# main_master.net
KiCad netlist of a schematic drawn in Altium Designer
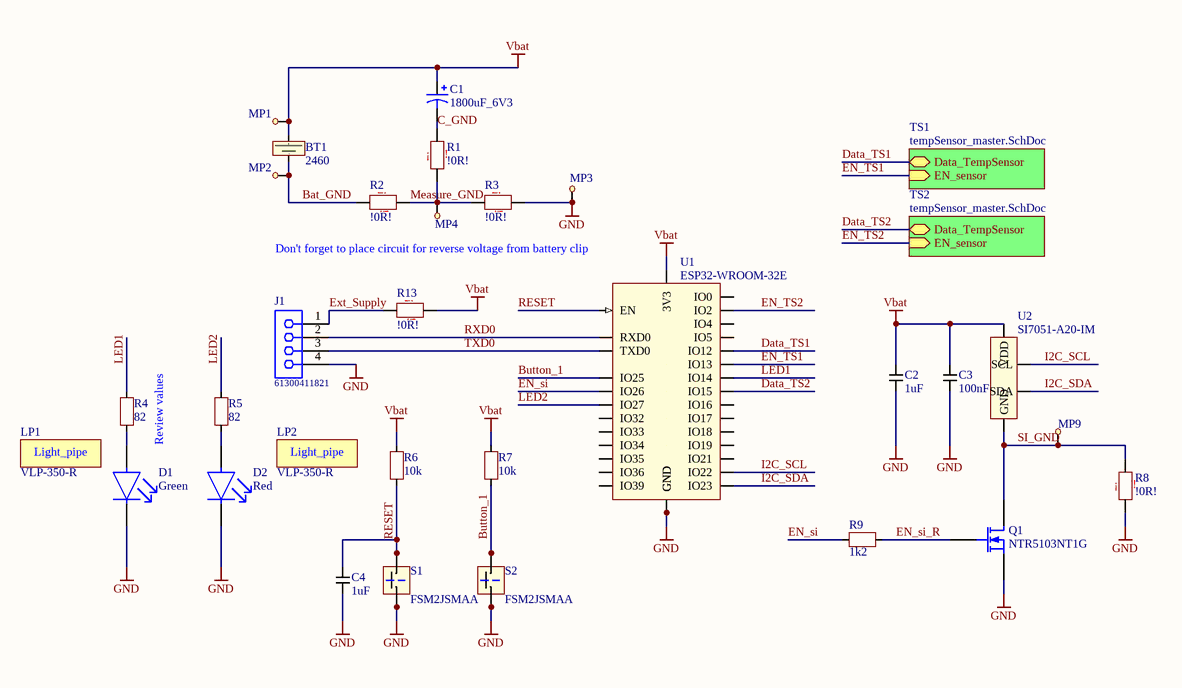
[diagram p0: main_master.SchDoc]

(export (version "E")
  (design (tool "Eeschema 10.0.6"))
  (components
    (comp (ref "BT1")
      (value "2460")
      (footprint "KEYSTONE_2410")
      (description "Battery Holder, AA x 1, Through Hole")
      (libsource (lib "Misc") (part "2460"))
    )
    (comp (ref "C1")
      (value "1800uF_6V3")
      (footprint "CAPAE109103X105M")
      (description "SMD Aluminium Electrolytic Capacitor, Radial Can, 1800 µF, 10 V, 0.092 ohm, TRV Series")
      (fields
        (field (name "MANUFACTURER PART NUMBER") "EEE-FN0J182UV")
        (field (name "MANUFACTURER") "Panasonic")
      )
      (libsource (lib "Capacitors_electrolytic") (part "1800uF_6V3"))
    )
    (comp (ref "C2")
      (value "1uF")
      (footprint "C1206")
      (description "1uF, 1206")
      (libsource (lib "Capacitors") (part "1uF,1206"))
    )
    (comp (ref "C3")
      (value "100nF")
      (footprint "C1206")
      (description "100nF, 1206")
      (libsource (lib "Capacitors") (part "100nF,1206"))
    )
    (comp (ref "C4")
      (value "1uF")
      (footprint "C1206")
      (description "1uF, 1206")
      (libsource (lib "Capacitors") (part "1uF,1206"))
    )
    (comp (ref "D1")
      (value "Green")
      (footprint "Kingbright_KPT-2012EC_0")
      (description "Standard LEDs - SMD GRN WATER CLEAR 0805")
      (fields
        (field (name "MANUFACTURER") "Kingbright")
        (field (name "MANUFACTURER PART NUMBER") "AP2012MGC")
      )
      (libsource (lib "LED_AND_DISPLAYS") (part "AP2012MGC"))
    )
    (comp (ref "D2")
      (value "Red")
      (footprint "Kingbright_KPT-2012EC_0")
      (description "KPT-2012EC -  LED, Low Power, Red, SMD, 0805 [2012 Metric], 30 mA, 2 V, 617 nm")
      (libsource (lib "LED_AND_DISPLAYS") (part "KPT-2012EC"))
    )
    (comp (ref "J1")
      (value "61300411821")
      (footprint "61300411821")
      (description "THT Vertical Socket Header WR-PHD, Pitch 2.54 mm, Single Row, 4 pins")
      (fields (field (name "PUBLISHER") "Wurth Elektronik"))
      (libsource (lib "Connectoren") (part "61300411821"))
    )
    (comp (ref "LP1")
      (value "VLP-350-R")
      (footprint "VLP-350-R")
      (description "LIGHT PIPE, SINGLE, ROUND, PCB")
      (fields (field (name "MANUFACTURER") "BIVAR"))
      (libsource (lib "Light_Pipes") (part "VLP-350-R"))
    )
    (comp (ref "LP2")
      (value "VLP-350-R")
      (footprint "VLP-350-R")
      (description "LIGHT PIPE, SINGLE, ROUND, PCB")
      (fields (field (name "MANUFACTURER") "BIVAR"))
      (libsource (lib "Light_Pipes") (part "VLP-350-R"))
    )
    (comp (ref "MP1")
      (value "Measure_point")
      (footprint "MeasurePoint_1.5mm")
      (description "Measurepoint")
      (libsource (lib "Misc") (part "Measure_point"))
    )
    (comp (ref "MP2")
      (value "Measure_point")
      (footprint "MeasurePoint_1.5mm")
      (description "Measurepoint")
      (libsource (lib "Misc") (part "Measure_point"))
    )
    (comp (ref "MP3")
      (value "Measure_point")
      (footprint "MeasurePoint_1.5mm")
      (description "Measurepoint")
      (libsource (lib "Misc") (part "Measure_point"))
    )
    (comp (ref "MP4")
      (value "Measure_point")
      (footprint "MeasurePoint_1.5mm")
      (description "Measurepoint")
      (libsource (lib "Misc") (part "Measure_point"))
    )
    (comp (ref "MP9")
      (value "Measure_point")
      (footprint "MeasurePoint_1.5mm")
      (description "Measurepoint")
      (libsource (lib "Misc") (part "Measure_point"))
    )
    (comp (ref "Q1")
      (value "NTR5103NT1G")
      (footprint "SOT23")
      (description "Power MOSFET, N Channel, 60 V, 260 mA, 1 ohm, SOT-23, Surface Mount")
      (fields (field (name "MANUFACTURER") "ON Semiconductor"))
      (libsource (lib "MOSFETS") (part "NTR5103NT1G"))
    )
    (comp (ref "R1")
      (value "!0R!")
      (footprint "R1206_Simple-Assemble")
      (description "normally shorted, but easy to change to an resistor footprint")
      (libsource (lib "") (part "0R, optional resistor_1"))
    )
    (comp (ref "R2")
      (value "!0R!")
      (footprint "R1206_Simple-Assemble")
      (description "normally shorted, but easy to change to an resistor footprint")
      (libsource (lib "Resistors") (part "0R, optional resistor"))
    )
    (comp (ref "R3")
      (value "!0R!")
      (footprint "R1206_Simple-Assemble")
      (description "normally shorted, but easy to change to an resistor footprint")
      (libsource (lib "Resistors") (part "0R, optional resistor"))
    )
    (comp (ref "R4")
      (value "82")
      (footprint "R1206_Simple-Assemble")
      (libsource (lib "Resistors") (part "82, 1206"))
    )
    (comp (ref "R5")
      (value "82")
      (footprint "R1206_Simple-Assemble")
      (libsource (lib "Resistors") (part "82, 1206"))
    )
    (comp (ref "R6")
      (value "10k")
      (footprint "R1206_Simple-Assemble")
      (description "10k, 1206, 250mW, 200V")
      (fields (field (name "POWER") "250mW"))
      (libsource (lib "Resistors") (part "10k, 1206"))
    )
    (comp (ref "R7")
      (value "10k")
      (footprint "R1206_Simple-Assemble")
      (description "10k, 1206, 250mW, 200V")
      (fields (field (name "POWER") "250mW"))
      (libsource (lib "Resistors") (part "10k, 1206"))
    )
    (comp (ref "R8")
      (value "!0R!")
      (footprint "R1206_Simple-Assemble")
      (description "normally shorted, but easy to change to an resistor footprint")
      (libsource (lib "") (part "0R, optional resistor_1"))
    )
    (comp (ref "R9")
      (value "1k2")
      (footprint "R1206_Simple-Assemble")
      (description "SMD Chip Resistor, 1206 [3216 Metric], 1 kohm, MCSR 12 Series, 200 V, Ceramic, 250 mW")
      (fields (field (name "POWER") "250mW"))
      (libsource (lib "Resistors") (part "1k2, 1206"))
    )
    (comp (ref "R13")
      (value "!0R!")
      (footprint "R1206_Simple-Assemble")
      (description "normally shorted, but easy to change to an resistor footprint")
      (libsource (lib "Resistors") (part "0R, optional resistor"))
    )
    (comp (ref "S1")
      (value "FSM2JSMAA")
      (footprint "FP-FSM2JSMAA-MFG")
      (description "Tactile Switch, FSMJSM Series, Top Actuated, Surface Mount, Round Button, 260 gf, 50mA at 24VDC")
      (fields (field (name "MANUFACTURER") "TE Connectivity"))
      (libsource (lib "Misc") (part "FSM2JSMAA"))
    )
    (comp (ref "S2")
      (value "FSM2JSMAA")
      (footprint "FP-FSM2JSMAA-MFG")
      (description "Tactile Switch, FSMJSM Series, Top Actuated, Surface Mount, Round Button, 260 gf, 50mA at 24VDC")
      (fields (field (name "MANUFACTURER") "TE Connectivity"))
      (libsource (lib "Misc") (part "FSM2JSMAA"))
    )
    (comp (ref "U1")
      (value "ESP32-WROOM-32E")
      (footprint "ESP32­WROOM­32E")
      (description "USB-modules (802.11) SMD Module ESP32-WROOM-32E, ESP32-D0WD-V3, 16 MB SPI flash, PCB antenna")
      (libsource (lib "Misc") (part "ESP32-WROOM-32E(M113EH2800PH3Q0)"))
    )
    (comp (ref "U2")
      (value "SI7051-A20-IM")
      (footprint "3x3 6-pin DFN")
      (description "Temperature Sensor IC, Digital, ± 0.1°C, -40 °C, 125 °C, DFN, 6 Pins")
      (libsource (lib "IC's") (part "SI7051-A20-IM"))
    )
  )
  (nets
    (net (code "1") (name "/Bat_GND") (class "Default")
      (node (ref "BT1") (pin "2") (pinfunction "-_2") (pintype "passive"))
      (node (ref "MP2") (pin "1") (pinfunction "1_1") (pintype "passive"))
      (node (ref "R2") (pin "1") (pinfunction "1_1") (pintype "passive"))
    )
    (net (code "2") (name "/Button_1") (class "Default")
      (node (ref "R7") (pin "1") (pinfunction "1_1") (pintype "passive"))
      (node (ref "S2") (pin "2") (pinfunction "b_2") (pintype "passive"))
      (node (ref "S2") (pin "4") (pinfunction "d_4") (pintype "passive"))
      (node (ref "U1") (pin "10") (pinfunction "IO25_10") (pintype "bidirectional"))
    )
    (net (code "3") (name "/C_GND") (class "Default")
      (node (ref "C1") (pin "2") (pinfunction "2_2") (pintype "passive"))
      (node (ref "R1") (pin "2") (pinfunction "2_2") (pintype "passive"))
    )
    (net (code "4") (name "/Data_TS1") (class "Default")
      (node (ref "U1") (pin "14") (pinfunction "IO12_14") (pintype "bidirectional"))
    )
    (net (code "5") (name "/Data_TS2") (class "Default")
      (node (ref "U1") (pin "23") (pinfunction "IO15_23") (pintype "bidirectional"))
    )
    (net (code "6") (name "/EN_TS1") (class "Default")
      (node (ref "U1") (pin "16") (pinfunction "IO13_16") (pintype "bidirectional"))
    )
    (net (code "7") (name "/EN_TS2") (class "Default")
      (node (ref "U1") (pin "24") (pinfunction "IO2_24") (pintype "bidirectional"))
    )
    (net (code "8") (name "/EN_si") (class "Default")
      (node (ref "R9") (pin "1") (pinfunction "1_1") (pintype "passive"))
      (node (ref "U1") (pin "11") (pinfunction "IO26_11") (pintype "bidirectional"))
    )
    (net (code "9") (name "/EN_si_R") (class "Default")
      (node (ref "Q1") (pin "1") (pinfunction "G_1") (pintype "passive"))
      (node (ref "R9") (pin "2") (pinfunction "2_2") (pintype "passive"))
    )
    (net (code "10") (name "/Ext_Supply") (class "Default")
      (node (ref "J1") (pin "1") (pinfunction "1_1") (pintype "passive"))
      (node (ref "R13") (pin "1") (pinfunction "1_1") (pintype "passive"))
    )
    (net (code "11") (name "/I2C_SCL") (class "Default")
      (node (ref "U1") (pin "36") (pinfunction "IO22_36") (pintype "bidirectional"))
      (node (ref "U2") (pin "6") (pinfunction "SCL_6") (pintype "bidirectional"))
    )
    (net (code "12") (name "/I2C_SDA") (class "Default")
      (node (ref "U1") (pin "37") (pinfunction "IO23_37") (pintype "bidirectional"))
      (node (ref "U2") (pin "1") (pinfunction "SDA_1") (pintype "bidirectional"))
    )
    (net (code "13") (name "/LED1") (class "Default")
      (node (ref "R4") (pin "2") (pinfunction "2_2") (pintype "passive"))
      (node (ref "U1") (pin "13") (pinfunction "IO14_13") (pintype "bidirectional"))
    )
    (net (code "14") (name "/LED2") (class "Default")
      (node (ref "R5") (pin "2") (pinfunction "2_2") (pintype "passive"))
      (node (ref "U1") (pin "12") (pinfunction "IO27_12") (pintype "bidirectional"))
    )
    (net (code "15") (name "/Measure_GND") (class "Default")
      (node (ref "MP4") (pin "1") (pinfunction "1_1") (pintype "passive"))
      (node (ref "R1") (pin "1") (pinfunction "1_1") (pintype "passive"))
      (node (ref "R2") (pin "2") (pinfunction "2_2") (pintype "passive"))
      (node (ref "R3") (pin "1") (pinfunction "1_1") (pintype "passive"))
    )
    (net (code "16") (name "/RESET") (class "Default")
      (node (ref "C4") (pin "2") (pinfunction "2_2") (pintype "passive"))
      (node (ref "R6") (pin "1") (pinfunction "1_1") (pintype "passive"))
      (node (ref "S1") (pin "2") (pinfunction "b_2") (pintype "passive"))
      (node (ref "S1") (pin "4") (pinfunction "d_4") (pintype "passive"))
      (node (ref "U1") (pin "3") (pinfunction "EN_3") (pintype "input"))
    )
    (net (code "17") (name "/RXD0") (class "Default")
      (node (ref "J1") (pin "2") (pinfunction "2_2") (pintype "passive"))
      (node (ref "U1") (pin "34") (pinfunction "RXD0_34") (pintype "bidirectional"))
    )
    (net (code "18") (name "/SI_GND") (class "Default")
      (node (ref "MP9") (pin "1") (pinfunction "1_1") (pintype "passive"))
      (node (ref "Q1") (pin "3") (pinfunction "D_3") (pintype "passive"))
      (node (ref "R8") (pin "2") (pinfunction "2_2") (pintype "passive"))
      (node (ref "U2") (pin "2") (pinfunction "GND_2") (pintype "power_in"))
    )
    (net (code "19") (name "/TXD0") (class "Default")
      (node (ref "J1") (pin "3") (pinfunction "3_3") (pintype "passive"))
      (node (ref "U1") (pin "35") (pinfunction "TXD0_35") (pintype "bidirectional"))
    )
    (net (code "20") (name "GND") (class "Default")
      (node (ref "C2") (pin "1") (pinfunction "1_1") (pintype "passive"))
      (node (ref "C3") (pin "1") (pinfunction "1_1") (pintype "passive"))
      (node (ref "C4") (pin "1") (pinfunction "1_1") (pintype "passive"))
      (node (ref "D1") (pin "1") (pinfunction "C_1") (pintype "passive"))
      (node (ref "D2") (pin "1") (pinfunction "C_1") (pintype "passive"))
      (node (ref "J1") (pin "4") (pinfunction "4_4") (pintype "passive"))
      (node (ref "MP3") (pin "1") (pinfunction "1_1") (pintype "passive"))
      (node (ref "Q1") (pin "2") (pinfunction "S_2") (pintype "passive"))
      (node (ref "R3") (pin "2") (pinfunction "2_2") (pintype "passive"))
      (node (ref "R8") (pin "1") (pinfunction "1_1") (pintype "passive"))
      (node (ref "S1") (pin "1") (pinfunction "a_1") (pintype "passive"))
      (node (ref "S1") (pin "3") (pinfunction "c_3") (pintype "passive"))
      (node (ref "S2") (pin "1") (pinfunction "a_1") (pintype "passive"))
      (node (ref "S2") (pin "3") (pinfunction "c_3") (pintype "passive"))
      (node (ref "U1") (pin "1") (pinfunction "GND_1") (pintype "power_in"))
      (node (ref "U1") (pin "15") (pinfunction "GND_15") (pintype "power_in"))
      (node (ref "U1") (pin "38") (pinfunction "GND_38") (pintype "power_in"))
    )
    (net (code "21") (name "Net-(D1-A)") (class "Default")
      (node (ref "D1") (pin "2") (pinfunction "A_2") (pintype "passive"))
      (node (ref "R4") (pin "1") (pinfunction "1_1") (pintype "passive"))
    )
    (net (code "22") (name "Net-(D2-A)") (class "Default")
      (node (ref "D2") (pin "2") (pinfunction "A_2") (pintype "passive"))
      (node (ref "R5") (pin "1") (pinfunction "1_1") (pintype "passive"))
    )
    (net (code "23") (name "Vbat") (class "Default")
      (node (ref "BT1") (pin "1") (pinfunction "+_1") (pintype "passive"))
      (node (ref "C1") (pin "1") (pinfunction "1_1") (pintype "passive"))
      (node (ref "C2") (pin "2") (pinfunction "2_2") (pintype "passive"))
      (node (ref "C3") (pin "2") (pinfunction "2_2") (pintype "passive"))
      (node (ref "MP1") (pin "1") (pinfunction "1_1") (pintype "passive"))
      (node (ref "R13") (pin "2") (pinfunction "2_2") (pintype "passive"))
      (node (ref "R6") (pin "2") (pinfunction "2_2") (pintype "passive"))
      (node (ref "R7") (pin "2") (pinfunction "2_2") (pintype "passive"))
      (node (ref "U1") (pin "2") (pinfunction "3V3_2") (pintype "power_in"))
      (node (ref "U2") (pin "5") (pinfunction "VDD_5") (pintype "power_in"))
    )
    (net (code "24") (name "unconnected-(U1-IO0-Pad25)") (class "Default")
      (node (ref "U1") (pin "25") (pinfunction "IO0_25") (pintype "bidirectional"))
    )
    (net (code "25") (name "unconnected-(U1-IO4-Pad26)") (class "Default")
      (node (ref "U1") (pin "26") (pinfunction "IO4_26") (pintype "bidirectional"))
    )
    (net (code "26") (name "unconnected-(U1-IO5-Pad29)") (class "Default")
      (node (ref "U1") (pin "29") (pinfunction "IO5_29") (pintype "bidirectional"))
    )
    (net (code "27") (name "unconnected-(U1-IO16-Pad27)") (class "Default")
      (node (ref "U1") (pin "27") (pinfunction "IO16_27") (pintype "bidirectional"))
    )
    (net (code "28") (name "unconnected-(U1-IO17-Pad28)") (class "Default")
      (node (ref "U1") (pin "28") (pinfunction "IO17_28") (pintype "bidirectional"))
    )
    (net (code "29") (name "unconnected-(U1-IO18-Pad30)") (class "Default")
      (node (ref "U1") (pin "30") (pinfunction "IO18_30") (pintype "bidirectional"))
    )
    (net (code "30") (name "unconnected-(U1-IO19-Pad31)") (class "Default")
      (node (ref "U1") (pin "31") (pinfunction "IO19_31") (pintype "bidirectional"))
    )
    (net (code "31") (name "unconnected-(U1-IO21-Pad33)") (class "Default")
      (node (ref "U1") (pin "33") (pinfunction "IO21_33") (pintype "bidirectional"))
    )
    (net (code "32") (name "unconnected-(U1-IO32-Pad8)") (class "Default")
      (node (ref "U1") (pin "8") (pinfunction "IO32_8") (pintype "bidirectional"))
    )
    (net (code "33") (name "unconnected-(U1-IO33-Pad9)") (class "Default")
      (node (ref "U1") (pin "9") (pinfunction "IO33_9") (pintype "bidirectional"))
    )
    (net (code "34") (name "unconnected-(U1-IO34-Pad6)") (class "Default")
      (node (ref "U1") (pin "6") (pinfunction "IO34_6") (pintype "bidirectional"))
    )
    (net (code "35") (name "unconnected-(U1-IO35-Pad7)") (class "Default")
      (node (ref "U1") (pin "7") (pinfunction "IO35_7") (pintype "bidirectional"))
    )
    (net (code "36") (name "unconnected-(U1-IO36-Pad4)") (class "Default")
      (node (ref "U1") (pin "4") (pinfunction "IO36_4") (pintype "bidirectional"))
    )
    (net (code "37") (name "unconnected-(U1-IO39-Pad5)") (class "Default")
      (node (ref "U1") (pin "5") (pinfunction "IO39_5") (pintype "bidirectional"))
    )
    (net (code "38") (name "unconnected-(U1-NC-Pad17)") (class "Default")
      (node (ref "U1") (pin "17") (pinfunction "NC_17") (pintype "tri_state"))
    )
    (net (code "39") (name "unconnected-(U1-NC-Pad18)") (class "Default")
      (node (ref "U1") (pin "18") (pinfunction "NC_18") (pintype "tri_state"))
    )
    (net (code "40") (name "unconnected-(U1-NC-Pad19)") (class "Default")
      (node (ref "U1") (pin "19") (pinfunction "NC_19") (pintype "tri_state"))
    )
    (net (code "41") (name "unconnected-(U1-NC-Pad20)") (class "Default")
      (node (ref "U1") (pin "20") (pinfunction "NC_20") (pintype "tri_state"))
    )
    (net (code "42") (name "unconnected-(U1-NC-Pad21)") (class "Default")
      (node (ref "U1") (pin "21") (pinfunction "NC_21") (pintype "tri_state"))
    )
    (net (code "43") (name "unconnected-(U1-NC-Pad22)") (class "Default")
      (node (ref "U1") (pin "22") (pinfunction "NC_22") (pintype "tri_state"))
    )
    (net (code "44") (name "unconnected-(U1-NC-Pad32)") (class "Default")
      (node (ref "U1") (pin "32") (pinfunction "NC_32") (pintype "tri_state"))
    )
  )
)
